# TeensyBreakout.net
KiCad netlist of a schematic drawn in EAGLE
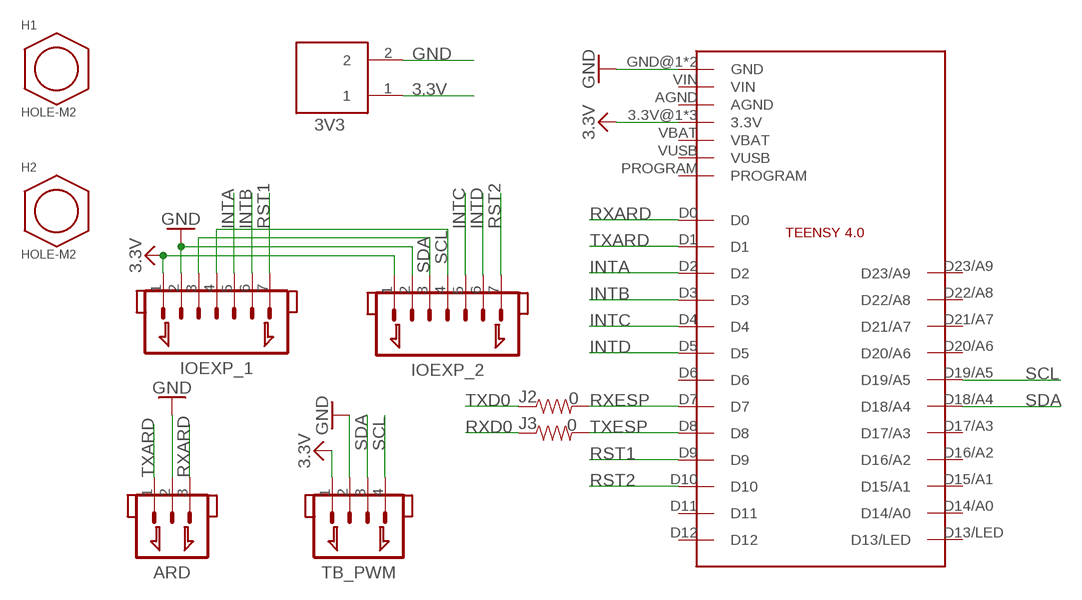
[diagram p0: schematic, sheet 1]
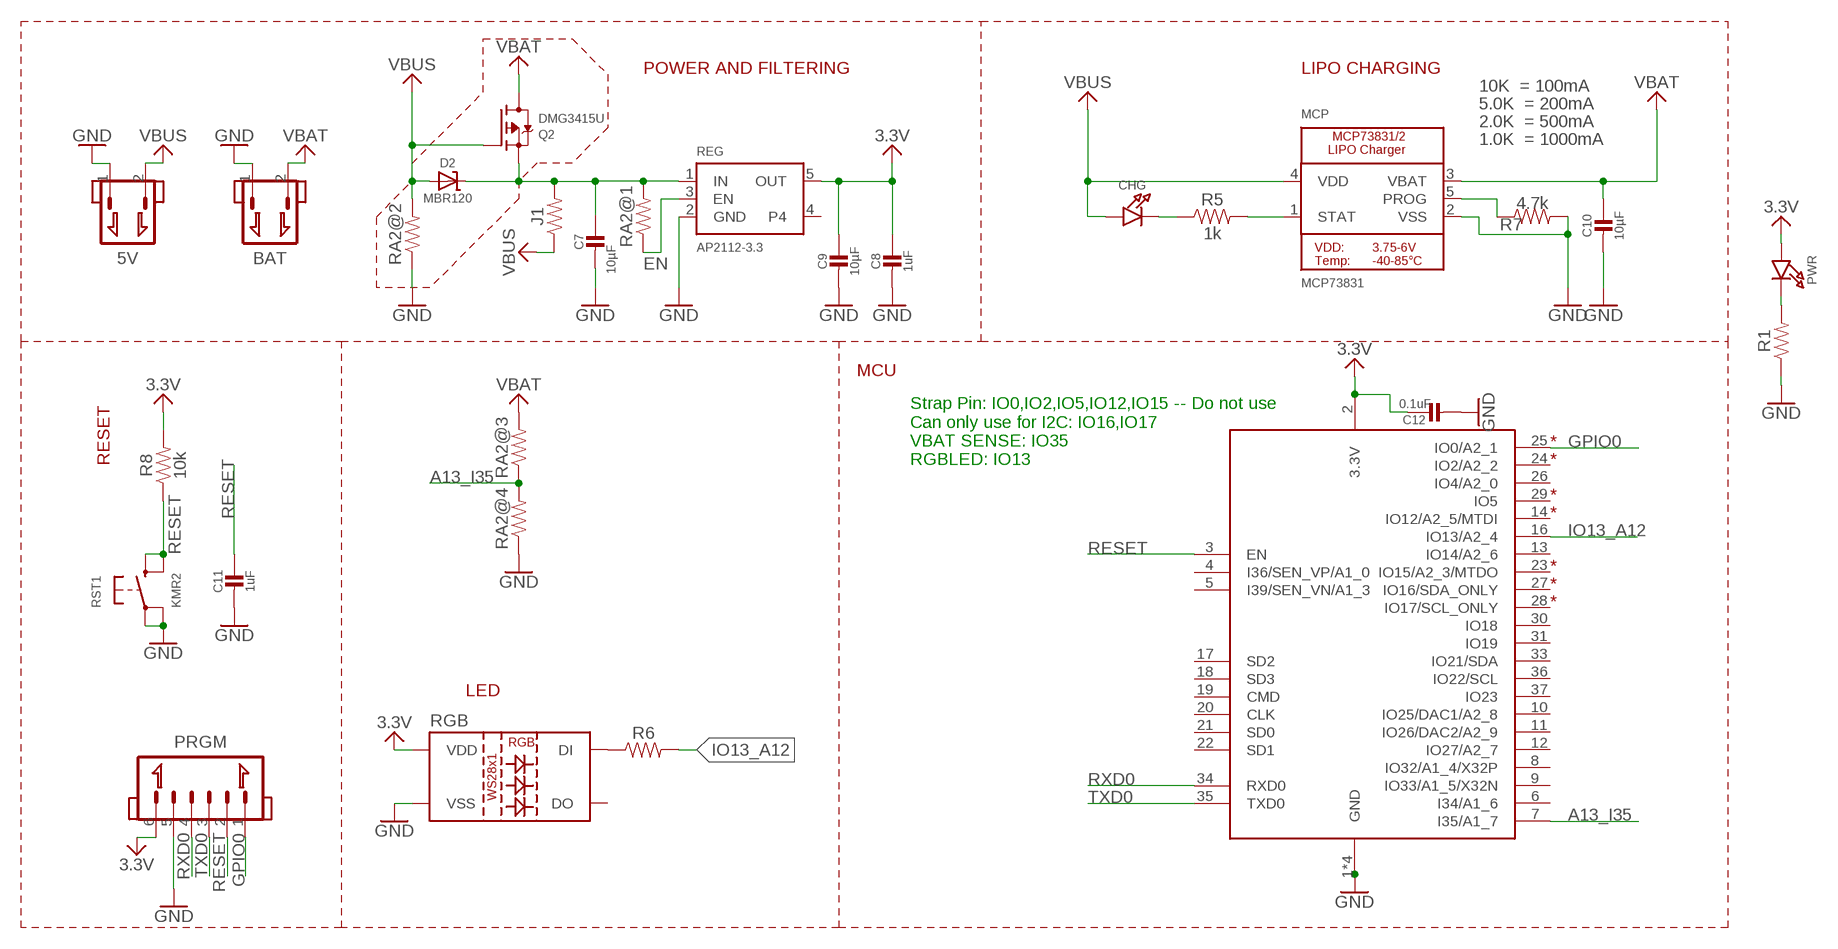
[diagram p1: schematic, sheet 2]

(export (version "E")
  (design (tool "Eeschema 10.0.6"))
  (components
    (comp (ref "5V")
      (value "JST_PH_2.0_2P")
      (footprint "eagle-import:JST_PH_2.0_2P")
      (libsource (lib "eagle-import") (part "JST_PH_2.0_2P"))
    )
    (comp (ref "BAT")
      (value "JSTPH")
      (footprint "eagle-import:JST_PH_2.0_2P")
      (libsource (lib "eagle-import") (part "JST_PH_2.0_2P"))
    )
    (comp (ref "C7")
      (value "10µF")
      (footprint "eagle-import:0805")
      (libsource (lib "eagle-import") (part "CAP_CERAMIC_0805"))
    )
    (comp (ref "C8")
      (value "1uF")
      (footprint "eagle-import:0603")
      (libsource (lib "eagle-import") (part "CAP_CERAMIC_0603"))
    )
    (comp (ref "C9")
      (value "10µF")
      (footprint "eagle-import:0603")
      (libsource (lib "eagle-import") (part "CAP_CERAMIC_0603"))
    )
    (comp (ref "C10")
      (value "10µF")
      (footprint "eagle-import:0805")
      (libsource (lib "eagle-import") (part "CAP_CERAMIC_0805"))
    )
    (comp (ref "C11")
      (value "1uF")
      (footprint "eagle-import:0603")
      (libsource (lib "eagle-import") (part "CAP_CERAMIC_0603"))
    )
    (comp (ref "C12")
      (value "0.1uF")
      (footprint "eagle-import:0603")
      (libsource (lib "eagle-import") (part "CAP_CERAMIC_0603"))
    )
    (comp (ref "CHG")
      (value "LED0603")
      (footprint "eagle-import:CHIPLED_0603")
      (libsource (lib "eagle-import") (part "LED0603"))
    )
    (comp (ref "D2")
      (value "MBR120")
      (footprint "eagle-import:SOD-123")
      (libsource (lib "eagle-import") (part "DIODE-SCHOTTKYSOD-123"))
    )
    (comp (ref "J1")
      (value "RESISTOR0603")
      (footprint "eagle-import:0603")
      (libsource (lib "eagle-import") (part "RESISTOR0603"))
    )
    (comp (ref "MCP")
      (value "MCP73831")
      (footprint "eagle-import:MICROBUILDER_SOT23-5")
      (libsource (lib "eagle-import") (part "MCP73831/2"))
    )
    (comp (ref "PRGM")
      (value "JST_1.25_6P")
      (footprint "eagle-import:JST1.25_6P")
      (libsource (lib "eagle-import") (part "JST_1.25_6P"))
    )
    (comp (ref "PWR")
      (value "LED0603")
      (footprint "eagle-import:CHIPLED_0603")
      (libsource (lib "eagle-import") (part "LED0603"))
    )
    (comp (ref "Q2")
      (value "DMG3415U")
      (footprint "eagle-import:SOT23-WIDE")
      (libsource (lib "eagle-import") (part "MOSFET-PWIDE"))
    )
    (comp (ref "R1")
      (value "RESISTOR0603")
      (footprint "eagle-import:0603")
      (libsource (lib "eagle-import") (part "RESISTOR0603"))
    )
    (comp (ref "R5")
      (value "1k")
      (footprint "eagle-import:0603")
      (libsource (lib "eagle-import") (part "RESISTOR0603"))
    )
    (comp (ref "R6")
      (value "RESISTOR0603")
      (footprint "eagle-import:0603")
      (libsource (lib "eagle-import") (part "RESISTOR0603"))
    )
    (comp (ref "R7")
      (value "4.7k")
      (footprint "eagle-import:0603")
      (libsource (lib "eagle-import") (part "RESISTOR0603"))
    )
    (comp (ref "R8")
      (value "10k")
      (footprint "eagle-import:0603")
      (libsource (lib "eagle-import") (part "RESISTOR0603"))
    )
    (comp (ref "RA2")
      (value "RESISTOR_ARRAY_1206_SEPARATE_REVERSE")
      (footprint "eagle-import:RESCAF80P320X160X60-8N")
      (libsource (lib "eagle-import") (part "RESISTOR_ARRAY_1206_SEPARATE_REVERSE"))
    )
    (comp (ref "REG")
      (value "AP2112-3.3")
      (footprint "eagle-import:MICROBUILDER_SOT23-5")
      (libsource (lib "eagle-import") (part "VREG_SOT23-5"))
    )
    (comp (ref "RGB")
      (value "LED_WS2812")
      (footprint "eagle-import:LED-TRICOLOR-5050-IC")
      (libsource (lib "eagle-import") (part "LED_WS2812"))
    )
    (comp (ref "RST1")
      (value "KMR2")
      (footprint "eagle-import:BTN_KMR2_4.6X2.8")
      (libsource (lib "eagle-import") (part "SWITCH_TACT_SMT4.6X2.8"))
    )
    (comp (ref "X1")
      (value "ESP32_WROOM32")
      (footprint "eagle-import:WROOM32")
      (libsource (lib "eagle-import") (part "ESP32_WROOM32"))
    )
    (comp (ref "3V3")
      (value "TERMINAL")
      (footprint "eagle-import:ED555_2DS")
      (libsource (lib "eagle-import") (part "TERMINAL"))
    )
    (comp (ref "ARD")
      (value "JST_1.25_3P")
      (footprint "eagle-import:JST1.25_3P")
      (libsource (lib "eagle-import") (part "JST_1.25_3P"))
    )
    (comp (ref "H1")
      (value "HOLE-M2")
      (footprint "eagle-import:M2")
      (libsource (lib "eagle-import") (part "HOLE-M2"))
    )
    (comp (ref "H2")
      (value "HOLE-M2")
      (footprint "eagle-import:M2")
      (libsource (lib "eagle-import") (part "HOLE-M2"))
    )
    (comp (ref "IOEXP_1")
      (value "JST_1.25_7P")
      (footprint "eagle-import:JST1.25_7P")
      (libsource (lib "eagle-import") (part "JST_1.25_7P"))
    )
    (comp (ref "IOEXP_2")
      (value "JST_1.25_7P")
      (footprint "eagle-import:JST1.25_7P")
      (libsource (lib "eagle-import") (part "JST_1.25_7P"))
    )
    (comp (ref "J2")
      (value "0")
      (footprint "eagle-import:0603")
      (libsource (lib "eagle-import") (part "RESISTOR0603"))
    )
    (comp (ref "J3")
      (value "0")
      (footprint "eagle-import:0603")
      (libsource (lib "eagle-import") (part "RESISTOR0603"))
    )
    (comp (ref "TB_PWM")
      (value "JST_1.25_4P")
      (footprint "eagle-import:JST1.25_4P")
      (libsource (lib "eagle-import") (part "JST_1.25_4P"))
    )
    (comp (ref "U$1")
      (value "TEENSY4.0")
      (footprint "eagle-import:TEENSY4.0")
      (libsource (lib "eagle-import") (part "TEENSY4.0"))
    )
  )
  (nets
    (net (code "1") (name "3.3V") (class "Default")
      (node (ref "3V3") (pin "1") (pinfunction "1_1") (pintype "bidirectional"))
      (node (ref "C12") (pin "1") (pinfunction "1_1") (pintype "passive"))
      (node (ref "C8") (pin "1") (pinfunction "1_1") (pintype "passive"))
      (node (ref "C9") (pin "1") (pinfunction "1_1") (pintype "passive"))
      (node (ref "IOEXP_1") (pin "1") (pinfunction "1_1") (pintype "passive"))
      (node (ref "IOEXP_2") (pin "1") (pinfunction "1_1") (pintype "passive"))
      (node (ref "PRGM") (pin "6") (pinfunction "6_6") (pintype "passive"))
      (node (ref "PWR") (pin "A") (pinfunction "A_A") (pintype "passive"))
      (node (ref "R8") (pin "2") (pinfunction "2_2") (pintype "passive"))
      (node (ref "REG") (pin "5") (pinfunction "OUT_5") (pintype "passive"))
      (node (ref "RGB") (pin "VDD") (pinfunction "VDD_VDD") (pintype "bidirectional"))
      (node (ref "TB_PWM") (pin "1") (pinfunction "1_1") (pintype "passive"))
      (node (ref "U$1") (pin "3.3V@1") (pinfunction "3.3V_3.3V@1") (pintype "bidirectional"))
      (node (ref "U$1") (pin "3.3V@2") (pinfunction "3.3V_3.3V@2") (pintype "bidirectional"))
      (node (ref "U$1") (pin "ON/OFF") (pinfunction "3.3V_ON/OFF") (pintype "bidirectional"))
      (node (ref "X1") (pin "2") (pinfunction "3.3V_2") (pintype "power_in"))
    )
    (net (code "2") (name "A13_I35") (class "Default")
      (node (ref "RA2") (pin "4") (pinfunction "2_4") (pintype "passive"))
      (node (ref "RA2") (pin "6") (pinfunction "1_6") (pintype "passive"))
      (node (ref "X1") (pin "7") (pinfunction "I35/A1_7_7") (pintype "bidirectional"))
    )
    (net (code "3") (name "EN") (class "Default")
      (node (ref "RA2") (pin "8") (pinfunction "1_8") (pintype "passive"))
      (node (ref "REG") (pin "3") (pinfunction "EN_3") (pintype "input"))
    )
    (net (code "4") (name "GND") (class "Default")
      (node (ref "3V3") (pin "2") (pinfunction "2_2") (pintype "bidirectional"))
      (node (ref "5V") (pin "1") (pinfunction "1_1") (pintype "passive"))
      (node (ref "ARD") (pin "2") (pinfunction "2_2") (pintype "passive"))
      (node (ref "BAT") (pin "1") (pinfunction "1_1") (pintype "passive"))
      (node (ref "C10") (pin "2") (pinfunction "2_2") (pintype "passive"))
      (node (ref "C11") (pin "2") (pinfunction "2_2") (pintype "passive"))
      (node (ref "C12") (pin "2") (pinfunction "2_2") (pintype "passive"))
      (node (ref "C7") (pin "2") (pinfunction "2_2") (pintype "passive"))
      (node (ref "C8") (pin "2") (pinfunction "2_2") (pintype "passive"))
      (node (ref "C9") (pin "2") (pinfunction "2_2") (pintype "passive"))
      (node (ref "IOEXP_1") (pin "2") (pinfunction "2_2") (pintype "passive"))
      (node (ref "IOEXP_2") (pin "2") (pinfunction "2_2") (pintype "passive"))
      (node (ref "MCP") (pin "2") (pinfunction "VSS_2") (pintype "input"))
      (node (ref "PRGM") (pin "5") (pinfunction "5_5") (pintype "passive"))
      (node (ref "R1") (pin "1") (pinfunction "1_1") (pintype "passive"))
      (node (ref "R7") (pin "2") (pinfunction "2_2") (pintype "passive"))
      (node (ref "RA2") (pin "5") (pinfunction "1_5") (pintype "passive"))
      (node (ref "RA2") (pin "7") (pinfunction "1_7") (pintype "passive"))
      (node (ref "REG") (pin "2") (pinfunction "GND_2") (pintype "input"))
      (node (ref "RGB") (pin "VSS") (pinfunction "VSS_VSS") (pintype "bidirectional"))
      (node (ref "RST1") (pin "A") (pinfunction "P_A") (pintype "passive"))
      (node (ref "RST1") (pin "A'") (pinfunction "P1_A'") (pintype "passive"))
      (node (ref "TB_PWM") (pin "2") (pinfunction "2_2") (pintype "passive"))
      (node (ref "U$1") (pin "GND@1") (pinfunction "GND_GND@1") (pintype "bidirectional"))
      (node (ref "U$1") (pin "GND@2") (pinfunction "GND_GND@2") (pintype "bidirectional"))
      (node (ref "X1") (pin "1") (pinfunction "GND_1") (pintype "power_in"))
      (node (ref "X1") (pin "15") (pinfunction "GND_15") (pintype "power_in"))
      (node (ref "X1") (pin "38") (pinfunction "GND_38") (pintype "power_in"))
      (node (ref "X1") (pin "P$1") (pinfunction "GND_P$1") (pintype "power_in"))
    )
    (net (code "5") (name "GPIO0") (class "Default")
      (node (ref "PRGM") (pin "1") (pinfunction "1_1") (pintype "passive"))
      (node (ref "X1") (pin "25") (pinfunction "IO0/A2_1_25") (pintype "bidirectional"))
    )
    (net (code "6") (name "INTA") (class "Default")
      (node (ref "IOEXP_1") (pin "5") (pinfunction "5_5") (pintype "passive"))
      (node (ref "U$1") (pin "D2") (pinfunction "D2_D2") (pintype "bidirectional"))
    )
    (net (code "7") (name "INTB") (class "Default")
      (node (ref "IOEXP_1") (pin "6") (pinfunction "6_6") (pintype "passive"))
      (node (ref "U$1") (pin "D3") (pinfunction "D3_D3") (pintype "bidirectional"))
    )
    (net (code "8") (name "INTC") (class "Default")
      (node (ref "IOEXP_2") (pin "5") (pinfunction "5_5") (pintype "passive"))
      (node (ref "U$1") (pin "D4") (pinfunction "D4_D4") (pintype "bidirectional"))
    )
    (net (code "9") (name "INTD") (class "Default")
      (node (ref "IOEXP_2") (pin "6") (pinfunction "6_6") (pintype "passive"))
      (node (ref "U$1") (pin "D5") (pinfunction "D5_D5") (pintype "bidirectional"))
    )
    (net (code "10") (name "IO13_A12") (class "Default")
      (node (ref "R6") (pin "2") (pinfunction "2_2") (pintype "passive"))
      (node (ref "X1") (pin "16") (pinfunction "IO13/A2_4_16") (pintype "bidirectional"))
    )
    (net (code "11") (name "Net-(CHG-PadC)") (class "Default")
      (node (ref "CHG") (pin "C") (pinfunction "C_C") (pintype "passive"))
      (node (ref "R5") (pin "1") (pinfunction "1_1") (pintype "passive"))
    )
    (net (code "12") (name "Net-(MCP-PROG)") (class "Default")
      (node (ref "MCP") (pin "5") (pinfunction "PROG_5") (pintype "input"))
      (node (ref "R7") (pin "1") (pinfunction "1_1") (pintype "passive"))
    )
    (net (code "13") (name "Net-(MCP-STAT)") (class "Default")
      (node (ref "MCP") (pin "1") (pinfunction "STAT_1") (pintype "output"))
      (node (ref "R5") (pin "2") (pinfunction "2_2") (pintype "passive"))
    )
    (net (code "14") (name "Net-(PWR-PadC)") (class "Default")
      (node (ref "PWR") (pin "C") (pinfunction "C_C") (pintype "passive"))
      (node (ref "R1") (pin "2") (pinfunction "2_2") (pintype "passive"))
    )
    (net (code "15") (name "Net-(Q2-S)") (class "Default")
      (node (ref "C7") (pin "1") (pinfunction "1_1") (pintype "passive"))
      (node (ref "D2") (pin "C") (pinfunction "C_C") (pintype "passive"))
      (node (ref "J1") (pin "2") (pinfunction "2_2") (pintype "passive"))
      (node (ref "Q2") (pin "2") (pinfunction "S_2") (pintype "passive"))
      (node (ref "RA2") (pin "1") (pinfunction "2_1") (pintype "passive"))
      (node (ref "REG") (pin "1") (pinfunction "IN_1") (pintype "input"))
    )
    (net (code "16") (name "Net-(RGB-DI)") (class "Default")
      (node (ref "R6") (pin "1") (pinfunction "1_1") (pintype "passive"))
      (node (ref "RGB") (pin "DIN") (pinfunction "DI_DIN") (pintype "bidirectional"))
    )
    (net (code "17") (name "RESET") (class "Default")
      (node (ref "C11") (pin "1") (pinfunction "1_1") (pintype "passive"))
      (node (ref "PRGM") (pin "2") (pinfunction "2_2") (pintype "passive"))
      (node (ref "R8") (pin "1") (pinfunction "1_1") (pintype "passive"))
      (node (ref "RST1") (pin "B") (pinfunction "S_B") (pintype "passive"))
      (node (ref "RST1") (pin "B'") (pinfunction "S1_B'") (pintype "passive"))
      (node (ref "X1") (pin "3") (pinfunction "EN_3") (pintype "input"))
    )
    (net (code "18") (name "RST1") (class "Default")
      (node (ref "IOEXP_1") (pin "7") (pinfunction "7_7") (pintype "passive"))
      (node (ref "U$1") (pin "D9") (pinfunction "D9_D9") (pintype "bidirectional"))
    )
    (net (code "19") (name "RST2") (class "Default")
      (node (ref "IOEXP_2") (pin "7") (pinfunction "7_7") (pintype "passive"))
      (node (ref "U$1") (pin "D10") (pinfunction "D10_D10") (pintype "bidirectional"))
    )
    (net (code "20") (name "RXARD") (class "Default")
      (node (ref "ARD") (pin "3") (pinfunction "3_3") (pintype "passive"))
      (node (ref "U$1") (pin "D0") (pinfunction "D0_D0") (pintype "bidirectional"))
    )
    (net (code "21") (name "RXD0") (class "Default")
      (node (ref "J3") (pin "1") (pinfunction "1_1") (pintype "passive"))
      (node (ref "PRGM") (pin "4") (pinfunction "4_4") (pintype "passive"))
      (node (ref "X1") (pin "34") (pinfunction "RXD0_34") (pintype "input"))
    )
    (net (code "22") (name "RXESP") (class "Default")
      (node (ref "J2") (pin "2") (pinfunction "2_2") (pintype "passive"))
      (node (ref "U$1") (pin "D7") (pinfunction "D7_D7") (pintype "bidirectional"))
    )
    (net (code "23") (name "SCL") (class "Default")
      (node (ref "IOEXP_1") (pin "4") (pinfunction "4_4") (pintype "passive"))
      (node (ref "IOEXP_2") (pin "4") (pinfunction "4_4") (pintype "passive"))
      (node (ref "TB_PWM") (pin "4") (pinfunction "4_4") (pintype "passive"))
      (node (ref "U$1") (pin "D19/A5") (pinfunction "D19/A5_D19/A5") (pintype "bidirectional"))
    )
    (net (code "24") (name "SDA") (class "Default")
      (node (ref "IOEXP_1") (pin "3") (pinfunction "3_3") (pintype "passive"))
      (node (ref "IOEXP_2") (pin "3") (pinfunction "3_3") (pintype "passive"))
      (node (ref "TB_PWM") (pin "3") (pinfunction "3_3") (pintype "passive"))
      (node (ref "U$1") (pin "D18/A4") (pinfunction "D18/A4_D18/A4") (pintype "bidirectional"))
    )
    (net (code "25") (name "TXARD") (class "Default")
      (node (ref "ARD") (pin "1") (pinfunction "1_1") (pintype "passive"))
      (node (ref "U$1") (pin "D1") (pinfunction "D1_D1") (pintype "bidirectional"))
    )
    (net (code "26") (name "TXD0") (class "Default")
      (node (ref "J2") (pin "1") (pinfunction "1_1") (pintype "passive"))
      (node (ref "PRGM") (pin "3") (pinfunction "3_3") (pintype "passive"))
      (node (ref "X1") (pin "35") (pinfunction "TXD0_35") (pintype "output"))
    )
    (net (code "27") (name "TXESP") (class "Default")
      (node (ref "J3") (pin "2") (pinfunction "2_2") (pintype "passive"))
      (node (ref "U$1") (pin "D8") (pinfunction "D8_D8") (pintype "bidirectional"))
    )
    (net (code "28") (name "VBAT") (class "Default")
      (node (ref "BAT") (pin "2") (pinfunction "2_2") (pintype "passive"))
      (node (ref "C10") (pin "1") (pinfunction "1_1") (pintype "passive"))
      (node (ref "MCP") (pin "3") (pinfunction "VBAT_3") (pintype "passive"))
      (node (ref "Q2") (pin "3") (pinfunction "D_3") (pintype "passive"))
      (node (ref "RA2") (pin "3") (pinfunction "2_3") (pintype "passive"))
    )
    (net (code "29") (name "VBUS") (class "Default")
      (node (ref "5V") (pin "2") (pinfunction "2_2") (pintype "passive"))
      (node (ref "CHG") (pin "A") (pinfunction "A_A") (pintype "passive"))
      (node (ref "D2") (pin "A") (pinfunction "A_A") (pintype "passive"))
      (node (ref "J1") (pin "1") (pinfunction "1_1") (pintype "passive"))
      (node (ref "MCP") (pin "4") (pinfunction "VDD_4") (pintype "input"))
      (node (ref "Q2") (pin "1") (pinfunction "G_1") (pintype "passive"))
      (node (ref "RA2") (pin "2") (pinfunction "2_2") (pintype "passive"))
    )
    (net (code "30") (name "unconnected-(REG-P4-Pad4)") (class "Default")
      (node (ref "REG") (pin "4") (pinfunction "P4_4") (pintype "bidirectional"))
    )
    (net (code "31") (name "unconnected-(RGB-DO-PadDOUT)") (class "Default")
      (node (ref "RGB") (pin "DOUT") (pinfunction "DO_DOUT") (pintype "bidirectional"))
    )
    (net (code "32") (name "unconnected-(U$1-PadAGND)") (class "Default")
      (node (ref "U$1") (pin "AGND") (pinfunction "AGND_AGND") (pintype "bidirectional"))
    )
    (net (code "33") (name "unconnected-(U$1-PadD6)") (class "Default")
      (node (ref "U$1") (pin "D6") (pinfunction "D6_D6") (pintype "bidirectional"))
    )
    (net (code "34") (name "unconnected-(U$1-PadD11)") (class "Default")
      (node (ref "U$1") (pin "D11") (pinfunction "D11_D11") (pintype "bidirectional"))
    )
    (net (code "35") (name "unconnected-(U$1-PadD12)") (class "Default")
      (node (ref "U$1") (pin "D12") (pinfunction "D12_D12") (pintype "bidirectional"))
    )
    (net (code "36") (name "unconnected-(U$1-PadD13{slash}LED)") (class "Default")
      (node (ref "U$1") (pin "D13/LED") (pinfunction "D13/LED_D13/LED") (pintype "bidirectional"))
    )
    (net (code "37") (name "unconnected-(U$1-PadD14{slash}A0)") (class "Default")
      (node (ref "U$1") (pin "D14/A0") (pinfunction "D14/A0_D14/A0") (pintype "bidirectional"))
    )
    (net (code "38") (name "unconnected-(U$1-PadD15{slash}A1)") (class "Default")
      (node (ref "U$1") (pin "D15/A1") (pinfunction "D15/A1_D15/A1") (pintype "bidirectional"))
    )
    (net (code "39") (name "unconnected-(U$1-PadD16{slash}A2)") (class "Default")
      (node (ref "U$1") (pin "D16/A2") (pinfunction "D16/A2_D16/A2") (pintype "bidirectional"))
    )
    (net (code "40") (name "unconnected-(U$1-PadD17{slash}A3)") (class "Default")
      (node (ref "U$1") (pin "D17/A3") (pinfunction "D17/A3_D17/A3") (pintype "bidirectional"))
    )
    (net (code "41") (name "unconnected-(U$1-PadD20{slash}A6)") (class "Default")
      (node (ref "U$1") (pin "D20/A6") (pinfunction "D20/A6_D20/A6") (pintype "bidirectional"))
    )
    (net (code "42") (name "unconnected-(U$1-PadD21{slash}A7)") (class "Default")
      (node (ref "U$1") (pin "D21/A7") (pinfunction "D21/A7_D21/A7") (pintype "bidirectional"))
    )
    (net (code "43") (name "unconnected-(U$1-PadD22{slash}A8)") (class "Default")
      (node (ref "U$1") (pin "D22/A8") (pinfunction "D22/A8_D22/A8") (pintype "bidirectional"))
    )
    (net (code "44") (name "unconnected-(U$1-PadD23{slash}A9)") (class "Default")
      (node (ref "U$1") (pin "D23/A9") (pinfunction "D23/A9_D23/A9") (pintype "bidirectional"))
    )
    (net (code "45") (name "unconnected-(U$1-PadPROGRAM)") (class "Default")
      (node (ref "U$1") (pin "PROGRAM") (pinfunction "PROGRAM_PROGRAM") (pintype "bidirectional"))
    )
    (net (code "46") (name "unconnected-(U$1-PadVBAT)") (class "Default")
      (node (ref "U$1") (pin "VBAT") (pinfunction "VBAT_VBAT") (pintype "bidirectional"))
    )
    (net (code "47") (name "unconnected-(U$1-PadVIN)") (class "Default")
      (node (ref "U$1") (pin "VIN") (pinfunction "VIN_VIN") (pintype "bidirectional"))
    )
    (net (code "48") (name "unconnected-(U$1-PadVUSB)") (class "Default")
      (node (ref "U$1") (pin "VUSB") (pinfunction "VUSB_VUSB") (pintype "bidirectional"))
    )
    (net (code "49") (name "unconnected-(X1-CLK-Pad20)") (class "Default")
      (node (ref "X1") (pin "20") (pinfunction "CLK_20") (pintype "no_connect"))
    )
    (net (code "50") (name "unconnected-(X1-CMD-Pad19)") (class "Default")
      (node (ref "X1") (pin "19") (pinfunction "CMD_19") (pintype "no_connect"))
    )
    (net (code "51") (name "unconnected-(X1-I34{slash}A1_6-Pad6)") (class "Default")
      (node (ref "X1") (pin "6") (pinfunction "I34/A1_6_6") (pintype "bidirectional"))
    )
    (net (code "52") (name "unconnected-(X1-I36{slash}SEN_VP{slash}A1_0-Pad4)") (class "Default")
      (node (ref "X1") (pin "4") (pinfunction "I36/SEN_VP/A1_0_4") (pintype "bidirectional"))
    )
    (net (code "53") (name "unconnected-(X1-I39{slash}SEN_VN{slash}A1_3-Pad5)") (class "Default")
      (node (ref "X1") (pin "5") (pinfunction "I39/SEN_VN/A1_3_5") (pintype "bidirectional"))
    )
    (net (code "54") (name "unconnected-(X1-IO2{slash}A2_2-Pad24)") (class "Default")
      (node (ref "X1") (pin "24") (pinfunction "IO2/A2_2_24") (pintype "bidirectional"))
    )
    (net (code "55") (name "unconnected-(X1-IO4{slash}A2_0-Pad26)") (class "Default")
      (node (ref "X1") (pin "26") (pinfunction "IO4/A2_0_26") (pintype "bidirectional"))
    )
    (net (code "56") (name "unconnected-(X1-IO5-Pad29)") (class "Default")
      (node (ref "X1") (pin "29") (pinfunction "IO5_29") (pintype "bidirectional"))
    )
    (net (code "57") (name "unconnected-(X1-IO12{slash}A2_5{slash}MTDI-Pad14)") (class "Default")
      (node (ref "X1") (pin "14") (pinfunction "IO12/A2_5/MTDI_14") (pintype "bidirectional"))
    )
    (net (code "58") (name "unconnected-(X1-IO14{slash}A2_6-Pad13)") (class "Default")
      (node (ref "X1") (pin "13") (pinfunction "IO14/A2_6_13") (pintype "bidirectional"))
    )
    (net (code "59") (name "unconnected-(X1-IO15{slash}A2_3{slash}MTDO-Pad23)") (class "Default")
      (node (ref "X1") (pin "23") (pinfunction "IO15/A2_3/MTDO_23") (pintype "bidirectional"))
    )
    (net (code "60") (name "unconnected-(X1-IO16{slash}SDA_ONLY-Pad27)") (class "Default")
      (node (ref "X1") (pin "27") (pinfunction "IO16/SDA_ONLY_27") (pintype "bidirectional"))
    )
    (net (code "61") (name "unconnected-(X1-IO17{slash}SCL_ONLY-Pad28)") (class "Default")
      (node (ref "X1") (pin "28") (pinfunction "IO17/SCL_ONLY_28") (pintype "bidirectional"))
    )
    (net (code "62") (name "unconnected-(X1-IO18-Pad30)") (class "Default")
      (node (ref "X1") (pin "30") (pinfunction "IO18_30") (pintype "bidirectional"))
    )
    (net (code "63") (name "unconnected-(X1-IO19-Pad31)") (class "Default")
      (node (ref "X1") (pin "31") (pinfunction "IO19_31") (pintype "bidirectional"))
    )
    (net (code "64") (name "unconnected-(X1-IO21{slash}SDA-Pad33)") (class "Default")
      (node (ref "X1") (pin "33") (pinfunction "IO21/SDA_33") (pintype "bidirectional"))
    )
    (net (code "65") (name "unconnected-(X1-IO22{slash}SCL-Pad36)") (class "Default")
      (node (ref "X1") (pin "36") (pinfunction "IO22/SCL_36") (pintype "bidirectional"))
    )
    (net (code "66") (name "unconnected-(X1-IO23-Pad37)") (class "Default")
      (node (ref "X1") (pin "37") (pinfunction "IO23_37") (pintype "bidirectional"))
    )
    (net (code "67") (name "unconnected-(X1-IO25{slash}DAC1{slash}A2_8-Pad10)") (class "Default")
      (node (ref "X1") (pin "10") (pinfunction "IO25/DAC1/A2_8_10") (pintype "bidirectional"))
    )
    (net (code "68") (name "unconnected-(X1-IO26{slash}DAC2{slash}A2_9-Pad11)") (class "Default")
      (node (ref "X1") (pin "11") (pinfunction "IO26/DAC2/A2_9_11") (pintype "bidirectional"))
    )
    (net (code "69") (name "unconnected-(X1-IO27{slash}A2_7-Pad12)") (class "Default")
      (node (ref "X1") (pin "12") (pinfunction "IO27/A2_7_12") (pintype "bidirectional"))
    )
    (net (code "70") (name "unconnected-(X1-IO32{slash}A1_4{slash}X32P-Pad8)") (class "Default")
      (node (ref "X1") (pin "8") (pinfunction "IO32/A1_4/X32P_8") (pintype "bidirectional"))
    )
    (net (code "71") (name "unconnected-(X1-IO33{slash}A1_5{slash}X32N-Pad9)") (class "Default")
      (node (ref "X1") (pin "9") (pinfunction "IO33/A1_5/X32N_9") (pintype "bidirectional"))
    )
    (net (code "72") (name "unconnected-(X1-SD0-Pad21)") (class "Default")
      (node (ref "X1") (pin "21") (pinfunction "SD0_21") (pintype "no_connect"))
    )
    (net (code "73") (name "unconnected-(X1-SD1-Pad22)") (class "Default")
      (node (ref "X1") (pin "22") (pinfunction "SD1_22") (pintype "no_connect"))
    )
    (net (code "74") (name "unconnected-(X1-SD2-Pad17)") (class "Default")
      (node (ref "X1") (pin "17") (pinfunction "SD2_17") (pintype "no_connect"))
    )
    (net (code "75") (name "unconnected-(X1-SD3-Pad18)") (class "Default")
      (node (ref "X1") (pin "18") (pinfunction "SD3_18") (pintype "no_connect"))
    )
  )
)
